# Input.net
KiCad netlist of a schematic drawn in Altium Designer
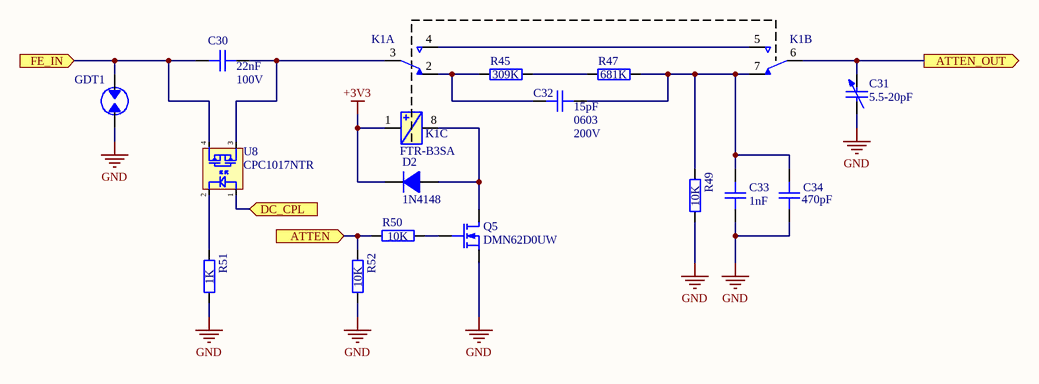
[diagram p0: Input.SchDoc]

(export (version "E")
  (design (tool "Eeschema 10.0.6"))
  (components
    (comp (ref "C30")
      (value "22nF")
      (footprint "GEN_C_0603")
      (fields (field (name "VOLTAGE RATING") "100V"))
      (libsource (lib "DSO") (part "CAP 22nF 100V X7R 0603"))
    )
    (comp (ref "C31")
      (value "5.5-20pF")
      (footprint "EW_TRIMCAP")
      (libsource (lib "DSO") (part "CAP TRIMMER 5.5-20PF 500V"))
    )
    (comp (ref "C32")
      (value "15pF")
      (footprint "GEN_C_0603")
      (fields (field (name "PACKAGE") "0603") (field (name "VOLTAGE RATING") "200V"))
      (libsource (lib "DSO") (part "CAP 15pF 200V C0G 0603"))
    )
    (comp (ref "C33")
      (value "1nF")
      (footprint "GEN_C_0402")
      (libsource (lib "DSO") (part "CAP 1nF 50V C0G 0402"))
    )
    (comp (ref "C34")
      (value "470pF")
      (footprint "GEN_C_0402")
      (libsource (lib "DSO") (part "CAP 470pF 50V C0G 0402"))
    )
    (comp (ref "D2") (value "1N4148") (footprint "GEN_SOD_323") (libsource (lib "DSO") (part "DIODE 1N4148")))
    (comp (ref "GDT1") (value "GDT") (footprint "BOU_2051") (libsource (lib "DSO") (part "GDT 90V")))
    (comp (ref "K1")
      (value "FTR-B3SA")
      (footprint "FUJ_FTR-B3SA")
      (libsource (lib "") (part "RELAY DPDT-NO FTR-B3SA_1"))
    )
    (comp (ref "Q5")
      (value "DMN62D0UW")
      (footprint "GEN_SOT_323")
      (libsource (lib "DSO") (part "NMOS DMN62D0UW"))
    )
    (comp (ref "R45")
      (value "309K")
      (footprint "GEN_R_0402")
      (fields (field (name "TOLERANCE") "1%"))
      (libsource (lib "DSO") (part "RES 309K OHM 1% 1/16W 0402"))
    )
    (comp (ref "R47")
      (value "681K")
      (footprint "GEN_R_0402")
      (fields (field (name "TOLERANCE") "1%"))
      (libsource (lib "DSO") (part "RES 681K OHM 1% 1/16W 0402"))
    )
    (comp (ref "R49")
      (value "10K")
      (footprint "GEN_R_0402")
      (fields (field (name "TOLERANCE") "1%"))
      (libsource (lib "DSO") (part "RES 10K OHM 1% 1/10W 0402"))
    )
    (comp (ref "R50")
      (value "10K")
      (footprint "GEN_R_0402")
      (fields (field (name "TOLERANCE") "1%"))
      (libsource (lib "") (part "RES 10K OHM 1% 1/10W 0402_1"))
    )
    (comp (ref "R51")
      (value "1K")
      (footprint "GEN_R_0402")
      (fields (field (name "TOLERANCE") "1%"))
      (libsource (lib "DSO") (part "RES 1K OHM 1% 1/10W 0402"))
    )
    (comp (ref "R52")
      (value "10K")
      (footprint "GEN_R_0402")
      (fields (field (name "TOLERANCE") "1%"))
      (libsource (lib "DSO") (part "RES 10K OHM 1% 1/10W 0402"))
    )
    (comp (ref "U8")
      (value "CPC1017NTR")
      (footprint "IXY_CPC1017")
      (libsource (lib "DSO") (part "SSR CPC1017NTR"))
    )
  )
  (nets
    (net (code "1") (name "+3V3") (class "Default")
      (node (ref "D2") (pin "1") (pinfunction "K_1") (pintype "passive"))
      (node (ref "K1") (pin "1") (pinfunction "1_1") (pintype "passive"))
    )
    (net (code "2") (name "/ATTEN") (class "Default")
      (node (ref "R50") (pin "2") (pinfunction "2_2") (pintype "passive"))
      (node (ref "R52") (pin "2") (pinfunction "2_2") (pintype "passive"))
    )
    (net (code "3") (name "/ATTEN_OUT") (class "Default")
      (node (ref "C31") (pin "1") (pinfunction "1_1") (pintype "passive"))
      (node (ref "K1") (pin "6") (pinfunction "6_6") (pintype "passive"))
    )
    (net (code "4") (name "/DC_CPL") (class "Default")
      (node (ref "U8") (pin "1") (pinfunction "1_1") (pintype "passive"))
    )
    (net (code "5") (name "/FE_IN") (class "Default")
      (node (ref "C30") (pin "2") (pinfunction "2_2") (pintype "passive"))
      (node (ref "GDT1") (pin "1") (pinfunction "1_1") (pintype "passive"))
      (node (ref "U8") (pin "4") (pinfunction "4_4") (pintype "passive"))
    )
    (net (code "6") (name "GND") (class "Default")
      (node (ref "C31") (pin "2") (pinfunction "2_2") (pintype "passive"))
      (node (ref "C33") (pin "1") (pinfunction "1_1") (pintype "passive"))
      (node (ref "C34") (pin "1") (pinfunction "1_1") (pintype "passive"))
      (node (ref "GDT1") (pin "2") (pinfunction "2_2") (pintype "passive"))
      (node (ref "Q5") (pin "3") (pinfunction "S_3") (pintype "passive"))
      (node (ref "R49") (pin "1") (pinfunction "1_1") (pintype "passive"))
      (node (ref "R51") (pin "1") (pinfunction "1_1") (pintype "passive"))
      (node (ref "R52") (pin "1") (pinfunction "1_1") (pintype "passive"))
    )
    (net (code "7") (name "Net-(C30-Pad1)") (class "Default")
      (node (ref "C30") (pin "1") (pinfunction "1_1") (pintype "passive"))
      (node (ref "K1") (pin "3") (pinfunction "3_3") (pintype "passive"))
      (node (ref "U8") (pin "3") (pinfunction "3_3") (pintype "passive"))
    )
    (net (code "8") (name "Net-(C32-Pad1)") (class "Default")
      (node (ref "C32") (pin "1") (pinfunction "1_1") (pintype "passive"))
      (node (ref "C33") (pin "2") (pinfunction "2_2") (pintype "passive"))
      (node (ref "C34") (pin "2") (pinfunction "2_2") (pintype "passive"))
      (node (ref "K1") (pin "7") (pinfunction "7_7") (pintype "passive"))
      (node (ref "R47") (pin "2") (pinfunction "2_2") (pintype "passive"))
      (node (ref "R49") (pin "2") (pinfunction "2_2") (pintype "passive"))
    )
    (net (code "9") (name "Net-(C32-Pad2)") (class "Default")
      (node (ref "C32") (pin "2") (pinfunction "2_2") (pintype "passive"))
      (node (ref "K1") (pin "2") (pinfunction "2_2") (pintype "passive"))
      (node (ref "R45") (pin "1") (pinfunction "1_1") (pintype "passive"))
    )
    (net (code "10") (name "Net-(D2-A)") (class "Default")
      (node (ref "D2") (pin "2") (pinfunction "A_2") (pintype "passive"))
      (node (ref "K1") (pin "8") (pinfunction "8_8") (pintype "passive"))
      (node (ref "Q5") (pin "1") (pinfunction "D_1") (pintype "passive"))
    )
    (net (code "11") (name "Net-(K1-Pad4)") (class "Default")
      (node (ref "K1") (pin "4") (pinfunction "4_4") (pintype "passive"))
      (node (ref "K1") (pin "5") (pinfunction "5_5") (pintype "passive"))
    )
    (net (code "12") (name "Net-(Q5-G)") (class "Default")
      (node (ref "Q5") (pin "2") (pinfunction "G_2") (pintype "passive"))
      (node (ref "R50") (pin "1") (pinfunction "1_1") (pintype "passive"))
    )
    (net (code "13") (name "Net-(R45-Pad2)") (class "Default")
      (node (ref "R45") (pin "2") (pinfunction "2_2") (pintype "passive"))
      (node (ref "R47") (pin "1") (pinfunction "1_1") (pintype "passive"))
    )
    (net (code "14") (name "Net-(R51-Pad2)") (class "Default")
      (node (ref "R51") (pin "2") (pinfunction "2_2") (pintype "passive"))
      (node (ref "U8") (pin "2") (pinfunction "2_2") (pintype "passive"))
    )
  )
)
